# motor-connections-power.net
KiCad netlist of a schematic drawn in Altium Designer
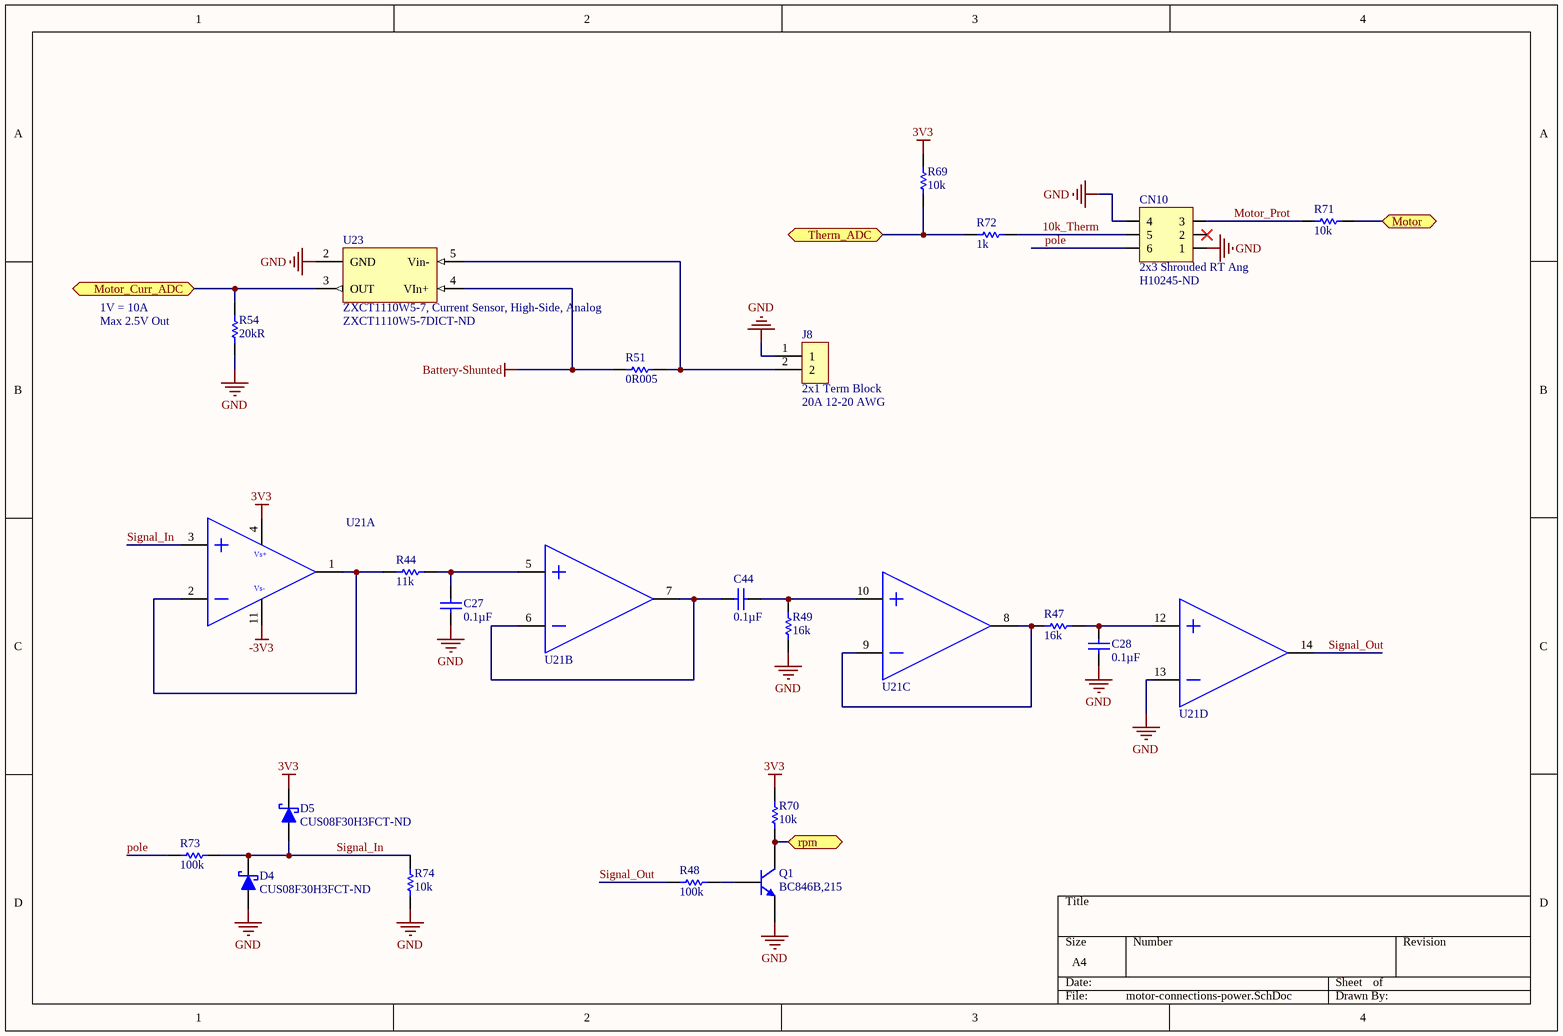
[diagram p0: motor-connections-power.SchDoc]

(export (version "E")
  (design (tool "Eeschema 10.0.6"))
  (components
    (comp (ref "C27")
      (value "0.1uF, 50V, 10%, X7R, 1608")
      (footprint "CAPC1608N(0603\")")
      (description "CAP CER 0.1UF 50V 10% X7R 1608 (0603)")
      (fields
        (field (name "MANUFACTURER") "Samsung Electro-Mechanics America, Inc")
        (field (name "MANUFACTURER PART NUMBER") "CL10B104KB8SFNC")
        (field (name "CAPACITANCE") "0.1µF")
      )
      (libsource (lib "AUVic_Integrated_Library_Capacitors") (part "0.1uF, 50V, 10%, X7R, 1608"))
    )
    (comp (ref "C28")
      (value "0.1uF, 50V, 10%, X7R, 1608")
      (footprint "CAPC1608N(0603\")")
      (description "CAP CER 0.1UF 50V 10% X7R 1608 (0603)")
      (fields
        (field (name "MANUFACTURER") "Samsung Electro-Mechanics America, Inc")
        (field (name "MANUFACTURER PART NUMBER") "CL10B104KB8SFNC")
        (field (name "CAPACITANCE") "0.1µF")
      )
      (libsource (lib "AUVic_Integrated_Library_Capacitors") (part "0.1uF, 50V, 10%, X7R, 1608"))
    )
    (comp (ref "C44")
      (value "0.1uF, 50V, 10%, X7R, 1608")
      (footprint "CAPC1608N(0603\")")
      (description "CAP CER 0.1UF 50V 10% X7R 1608 (0603)")
      (fields
        (field (name "MANUFACTURER") "Samsung Electro-Mechanics America, Inc")
        (field (name "MANUFACTURER PART NUMBER") "CL10B104KB8SFNC")
        (field (name "CAPACITANCE") "0.1µF")
      )
      (libsource (lib "AUVic_Integrated_Library_Capacitors") (part "0.1uF, 50V, 10%, X7R, 1608"))
    )
    (comp (ref "CN10")
      (value "2x3 Shrouded RT Ang")
      (footprint "HEADER, MALE, Shrouded, 6POS, 2MM, RT ANG,THT")
      (description "Header, Male, 2x3, Pitch: 0.1\" (2.54mm), THT")
      (fields
        (field (name "SUPPLIER PART NUMBER 1") "H10245-ND")
        (field (name "PUBLISHER") "AUVic")
        (field (name "REVIEWED BY") "*")
        (field (name "CREATED BY") "Andy Bates")
      )
      (libsource (lib "AUVic_Schematic_Library_Connectors") (part "Header, Male, 2x3 Conn, Shrouded, THT, 2MM RT ANG TIN"))
    )
    (comp (ref "D4")
      (value "CUS08F30H3FCT-ND")
      (footprint "SC-76")
      (description "Diode, Schottky, 30V, 800mA")
      (fields
        (field (name "SUPPLIER PART NUMBER 1") "CUS08F30H3FCT-ND")
        (field (name "CREATED BY") "Andy Bates")
        (field (name "PUBLISHER") "AUVic")
      )
      (libsource (lib "AUVic_Integrated_Library_Diodes") (part "CUS08F30H3FCT-ND"))
    )
    (comp (ref "D5")
      (value "CUS08F30H3FCT-ND")
      (footprint "SC-76")
      (description "Diode, Schottky, 30V, 800mA")
      (fields
        (field (name "SUPPLIER PART NUMBER 1") "CUS08F30H3FCT-ND")
        (field (name "CREATED BY") "Andy Bates")
        (field (name "PUBLISHER") "AUVic")
      )
      (libsource (lib "AUVic_Integrated_Library_Diodes") (part "CUS08F30H3FCT-ND"))
    )
    (comp (ref "J8")
      (value "2x1 Term Block")
      (footprint "2X1 Terminal Blocks Phoenix Contact 5mm")
      (fields (field (name "MADE BY") "Andy Bates"))
      (libsource (lib "AUVic_Integrated_Library_Connectors") (part "2x1 Terminal Block, 20A, 12-20AWG"))
    )
    (comp (ref "Q1")
      (value "BC846B,215")
      (footprint "SOT-23")
      (description "NPN 65V 100mA 250mW")
      (fields (field (name "PUBLISHER") "Andy Bates"))
      (libsource (lib "AUVic_Integrated_Library_Transistors") (part "BC846B,215"))
    )
    (comp (ref "R44")
      (value "11k")
      (footprint "RESC1608N(0603\")")
      (description "11kR, 1%, 1/10W, 0603 SMD")
      (fields (field (name "MADE BY") "Ashwin Sira"))
      (libsource (lib "AUVic_Integrated_Library_Resistors") (part "11kR, 1%, 1/10W, 0603 SMD"))
    )
    (comp (ref "R47")
      (value "16k")
      (footprint "RESC1608N(0603\")")
      (description "16kR, 1%, 1/10W, 0603 SMD")
      (fields (field (name "MADE BY") "Ashwin Sira"))
      (libsource (lib "AUVic_Integrated_Library_Resistors") (part "16kR, 1%, 1/10W, 0603 SMD"))
    )
    (comp (ref "R48")
      (value "100k")
      (footprint "RESC1608N(0603\")")
      (description "100kR, 1%, 1/10W, 0603 SMD")
      (fields (field (name "MADE BY") "Andy Bates"))
      (libsource (lib "AUVic_Integrated_Library_Resistors") (part "100kR, 1%, 1/10W, 0603 SMD"))
    )
    (comp (ref "R49")
      (value "16k")
      (footprint "RESC1608N(0603\")")
      (description "16kR, 1%, 1/10W, 0603 SMD")
      (fields (field (name "MADE BY") "Ashwin Sira"))
      (libsource (lib "AUVic_Integrated_Library_Resistors") (part "16kR, 1%, 1/10W, 0603 SMD"))
    )
    (comp (ref "R51")
      (value "0R005")
      (footprint "RESC6332N(2512\")")
      (description "0R005, 1%, 3W, 2512 SMD")
      (fields
        (field (name "MFG") "Riedon")
        (field (name "CREATED BY") "Andy Bates")
        (field (name "PUBLISHER") "AUVic")
      )
      (libsource (lib "AUVic_Integrated_Library_Resistors") (part "0R005, 1%, 3W, 2512 SMD"))
    )
    (comp (ref "R54")
      (value "20kR")
      (footprint "RESC1608N(0603\")")
      (description "20k, 1%, 1/10W, 0603, SMD")
      (fields (field (name "CREATED BY") "Andy Bates") (field (name "PUBLISHER") "AUVic"))
      (libsource (lib "AUVic_Integrated_Library_Resistors") (part "20k, 1%, 1/10W, 0603, SMD"))
    )
    (comp (ref "R69")
      (value "10k")
      (footprint "RESC1608N(0603\")")
      (description "10kR, 1%, 1/10W, 0603 SMD")
      (fields (field (name "MADE BY") "Ashwin Sira"))
      (libsource (lib "AUVic_Integrated_Library_Resistors") (part "10kR, 1%, 1/10W, 0603 SMD"))
    )
    (comp (ref "R70")
      (value "10k")
      (footprint "RESC1608N(0603\")")
      (description "10kR, 1%, 1/10W, 0603 SMD")
      (fields (field (name "MADE BY") "Ashwin Sira"))
      (libsource (lib "AUVic_Integrated_Library_Resistors") (part "10kR, 1%, 1/10W, 0603 SMD"))
    )
    (comp (ref "R71")
      (value "10k")
      (footprint "RESC1608N(0603\")")
      (description "10kR, 1%, 1/10W, 0603 SMD")
      (fields (field (name "MADE BY") "Ashwin Sira"))
      (libsource (lib "AUVic_Integrated_Library_Resistors") (part "10kR, 1%, 1/10W, 0603 SMD"))
    )
    (comp (ref "R72")
      (value "1k")
      (footprint "RESC1608N(0603\")")
      (description "1kR, 1%, 1/10W , 0603, SMD")
      (fields (field (name "CREATED BY") "Andy Bates") (field (name "PUBLISHER") "AUVic"))
      (libsource (lib "AUVic_Integrated_Library_Resistors") (part "1kR, 1%, 1/10W , 0603, SMD"))
    )
    (comp (ref "R73")
      (value "100k")
      (footprint "RESC1608N(0603\")")
      (description "100kR, 1%, 1/10W, 0603 SMD")
      (fields (field (name "MADE BY") "Andy Bates"))
      (libsource (lib "AUVic_Integrated_Library_Resistors") (part "100kR, 1%, 1/10W, 0603 SMD"))
    )
    (comp (ref "R74")
      (value "10k")
      (footprint "RESC1608N(0603\")")
      (description "10kR, 1%, 1/10W, 0603 SMD")
      (fields (field (name "MADE BY") "Ashwin Sira"))
      (libsource (lib "AUVic_Integrated_Library_Resistors") (part "10kR, 1%, 1/10W, 0603 SMD"))
    )
    (comp (ref "U21")
      (value "Quad Op Amp TSV324")
      (footprint "SOP-14")
      (description "TSV324")
      (fields (field (name "PUBLISHER") "Altium Limited") (field (name "CREATED BY") "Jordan"))
      (libsource (lib "AUVic_Schematic_Library_Op_amps") (part "Quad Op Amp TSV324"))
    )
    (comp (ref "U23")
      (value "ZXCT1110W5-7, Current Sensor, High-Side, Analog")
      (footprint "SOT23-5")
      (description "Diodes Incorporated, ZXCT1110W5-7")
      (fields
        (field (name "SUPPLIER PART NUMBER 1") "ZXCT1110W5-7DICT-ND")
        (field (name "CREATED BY") "Jacob Lower")
        (field (name "PUBLISHER") "AUVic")
      )
      (libsource (lib "AUVic_Schematic_Library_Sensors") (part "ZXCT1110W5-7, Current Sensor, High-Side, Analog"))
    )
  )
  (nets
    (net (code "1") (name "-3V3") (class "Default")
      (node (ref "U21") (pin "11") (pinfunction "Vcc-_11") (pintype "passive"))
    )
    (net (code "2") (name "/10k_Therm") (class "Default")
      (node (ref "CN10") (pin "5") (pinfunction "5_5") (pintype "passive"))
      (node (ref "R72") (pin "2") (pinfunction "2_2") (pintype "passive"))
    )
    (net (code "3") (name "/Motor") (class "Default")
      (node (ref "R71") (pin "1") (pinfunction "1_1") (pintype "passive"))
    )
    (net (code "4") (name "/Motor_Curr_ADC") (class "Default")
      (node (ref "R54") (pin "2") (pinfunction "2_2") (pintype "passive"))
      (node (ref "U23") (pin "3") (pinfunction "OUT_3") (pintype "output"))
    )
    (net (code "5") (name "/Motor_Prot") (class "Default")
      (node (ref "CN10") (pin "3") (pinfunction "3_3") (pintype "passive"))
      (node (ref "R71") (pin "2") (pinfunction "2_2") (pintype "passive"))
    )
    (net (code "6") (name "/Signal_In") (class "Default")
      (node (ref "D4") (pin "K") (pinfunction "Cathode_K") (pintype "passive"))
      (node (ref "D5") (pin "A") (pinfunction "Anode_A") (pintype "passive"))
      (node (ref "R73") (pin "1") (pinfunction "1_1") (pintype "passive"))
      (node (ref "R74") (pin "2") (pinfunction "2_2") (pintype "passive"))
      (node (ref "U21") (pin "3") (pinfunction "Non-Inverting_Input_1_3") (pintype "passive"))
    )
    (net (code "7") (name "/Signal_Out") (class "Default")
      (node (ref "R48") (pin "1") (pinfunction "1_1") (pintype "passive"))
      (node (ref "U21") (pin "14") (pinfunction "Output_4_14") (pintype "passive"))
    )
    (net (code "8") (name "/Therm_ADC") (class "Default")
      (node (ref "R69") (pin "1") (pinfunction "1_1") (pintype "passive"))
      (node (ref "R72") (pin "1") (pinfunction "1_1") (pintype "passive"))
    )
    (net (code "9") (name "/pole") (class "Default")
      (node (ref "CN10") (pin "6") (pinfunction "6_6") (pintype "passive"))
      (node (ref "R73") (pin "2") (pinfunction "2_2") (pintype "passive"))
    )
    (net (code "10") (name "/rpm") (class "Default")
      (node (ref "Q1") (pin "3") (pinfunction "C_3") (pintype "passive"))
      (node (ref "R70") (pin "1") (pinfunction "1_1") (pintype "passive"))
    )
    (net (code "11") (name "3V3") (class "Default")
      (node (ref "D5") (pin "K") (pinfunction "Cathode_K") (pintype "passive"))
      (node (ref "R69") (pin "2") (pinfunction "2_2") (pintype "passive"))
      (node (ref "R70") (pin "2") (pinfunction "2_2") (pintype "passive"))
      (node (ref "U21") (pin "4") (pinfunction "Vcc+_4") (pintype "passive"))
    )
    (net (code "12") (name "Battery-Shunted") (class "Default")
      (node (ref "R51") (pin "2") (pinfunction "2_2") (pintype "passive"))
      (node (ref "U23") (pin "4") (pinfunction "VIn+_4") (pintype "input"))
    )
    (net (code "13") (name "GND") (class "Default")
      (node (ref "C27") (pin "1") (pinfunction "Anode_1") (pintype "passive"))
      (node (ref "C28") (pin "1") (pinfunction "Anode_1") (pintype "passive"))
      (node (ref "CN10") (pin "1") (pinfunction "1_1") (pintype "passive"))
      (node (ref "CN10") (pin "4") (pinfunction "4_4") (pintype "passive"))
      (node (ref "D4") (pin "A") (pinfunction "Anode_A") (pintype "passive"))
      (node (ref "J8") (pin "1") (pinfunction "1_1") (pintype "passive"))
      (node (ref "Q1") (pin "2") (pinfunction "E_2") (pintype "passive"))
      (node (ref "R49") (pin "1") (pinfunction "1_1") (pintype "passive"))
      (node (ref "R54") (pin "1") (pinfunction "1_1") (pintype "passive"))
      (node (ref "R74") (pin "1") (pinfunction "1_1") (pintype "passive"))
      (node (ref "U21") (pin "13") (pinfunction "Inverting_Input_3_13") (pintype "passive"))
      (node (ref "U23") (pin "2") (pinfunction "GND_2") (pintype "power_in"))
    )
    (net (code "14") (name "Net-(C27-Cathode)") (class "Default")
      (node (ref "C27") (pin "2") (pinfunction "Cathode_2") (pintype "passive"))
      (node (ref "R44") (pin "2") (pinfunction "2_2") (pintype "passive"))
      (node (ref "U21") (pin "5") (pinfunction "Non-Inverting_Input_2_5") (pintype "passive"))
    )
    (net (code "15") (name "Net-(C28-Cathode)") (class "Default")
      (node (ref "C28") (pin "2") (pinfunction "Cathode_2") (pintype "passive"))
      (node (ref "R47") (pin "1") (pinfunction "1_1") (pintype "passive"))
      (node (ref "U21") (pin "12") (pinfunction "Non-Inverting_Input_4_12") (pintype "passive"))
    )
    (net (code "16") (name "Net-(C44-Anode)") (class "Default")
      (node (ref "C44") (pin "1") (pinfunction "Anode_1") (pintype "passive"))
      (node (ref "U21") (pin "6") (pinfunction "Inverting_Input_2_6") (pintype "passive"))
      (node (ref "U21") (pin "7") (pinfunction "Output_2_7") (pintype "passive"))
    )
    (net (code "17") (name "Net-(C44-Cathode)") (class "Default")
      (node (ref "C44") (pin "2") (pinfunction "Cathode_2") (pintype "passive"))
      (node (ref "R49") (pin "2") (pinfunction "2_2") (pintype "passive"))
      (node (ref "U21") (pin "10") (pinfunction "Non-Inverting_Input_3_10") (pintype "passive"))
    )
    (net (code "18") (name "Net-(Q1-B)") (class "Default")
      (node (ref "Q1") (pin "1") (pinfunction "B_1") (pintype "passive"))
      (node (ref "R48") (pin "2") (pinfunction "2_2") (pintype "passive"))
    )
    (net (code "19") (name "Net-(U21A-Inverting_Input_1)") (class "Default")
      (node (ref "R44") (pin "1") (pinfunction "1_1") (pintype "passive"))
      (node (ref "U21") (pin "1") (pinfunction "Output_1_1") (pintype "passive"))
      (node (ref "U21") (pin "2") (pinfunction "Inverting_Input_1_2") (pintype "passive"))
    )
    (net (code "20") (name "Net-(U21C-Inverting_Input_3)") (class "Default")
      (node (ref "R47") (pin "2") (pinfunction "2_2") (pintype "passive"))
      (node (ref "U21") (pin "8") (pinfunction "Output_3_8") (pintype "passive"))
      (node (ref "U21") (pin "9") (pinfunction "Inverting_Input_3_9") (pintype "passive"))
    )
    (net (code "21") (name "Net-(U23-Vin-)") (class "Default")
      (node (ref "J8") (pin "2") (pinfunction "2_2") (pintype "passive"))
      (node (ref "R51") (pin "1") (pinfunction "1_1") (pintype "passive"))
      (node (ref "U23") (pin "5") (pinfunction "Vin-_5") (pintype "input"))
    )
    (net (code "22") (name "unconnected-(CN10-Pad2)") (class "Default")
      (node (ref "CN10") (pin "2") (pinfunction "2_2") (pintype "passive+no_connect"))
    )
  )
)
